# Zio_Qwiic_LoRa_Dev_Board.net
KiCad netlist of a schematic drawn in EAGLE
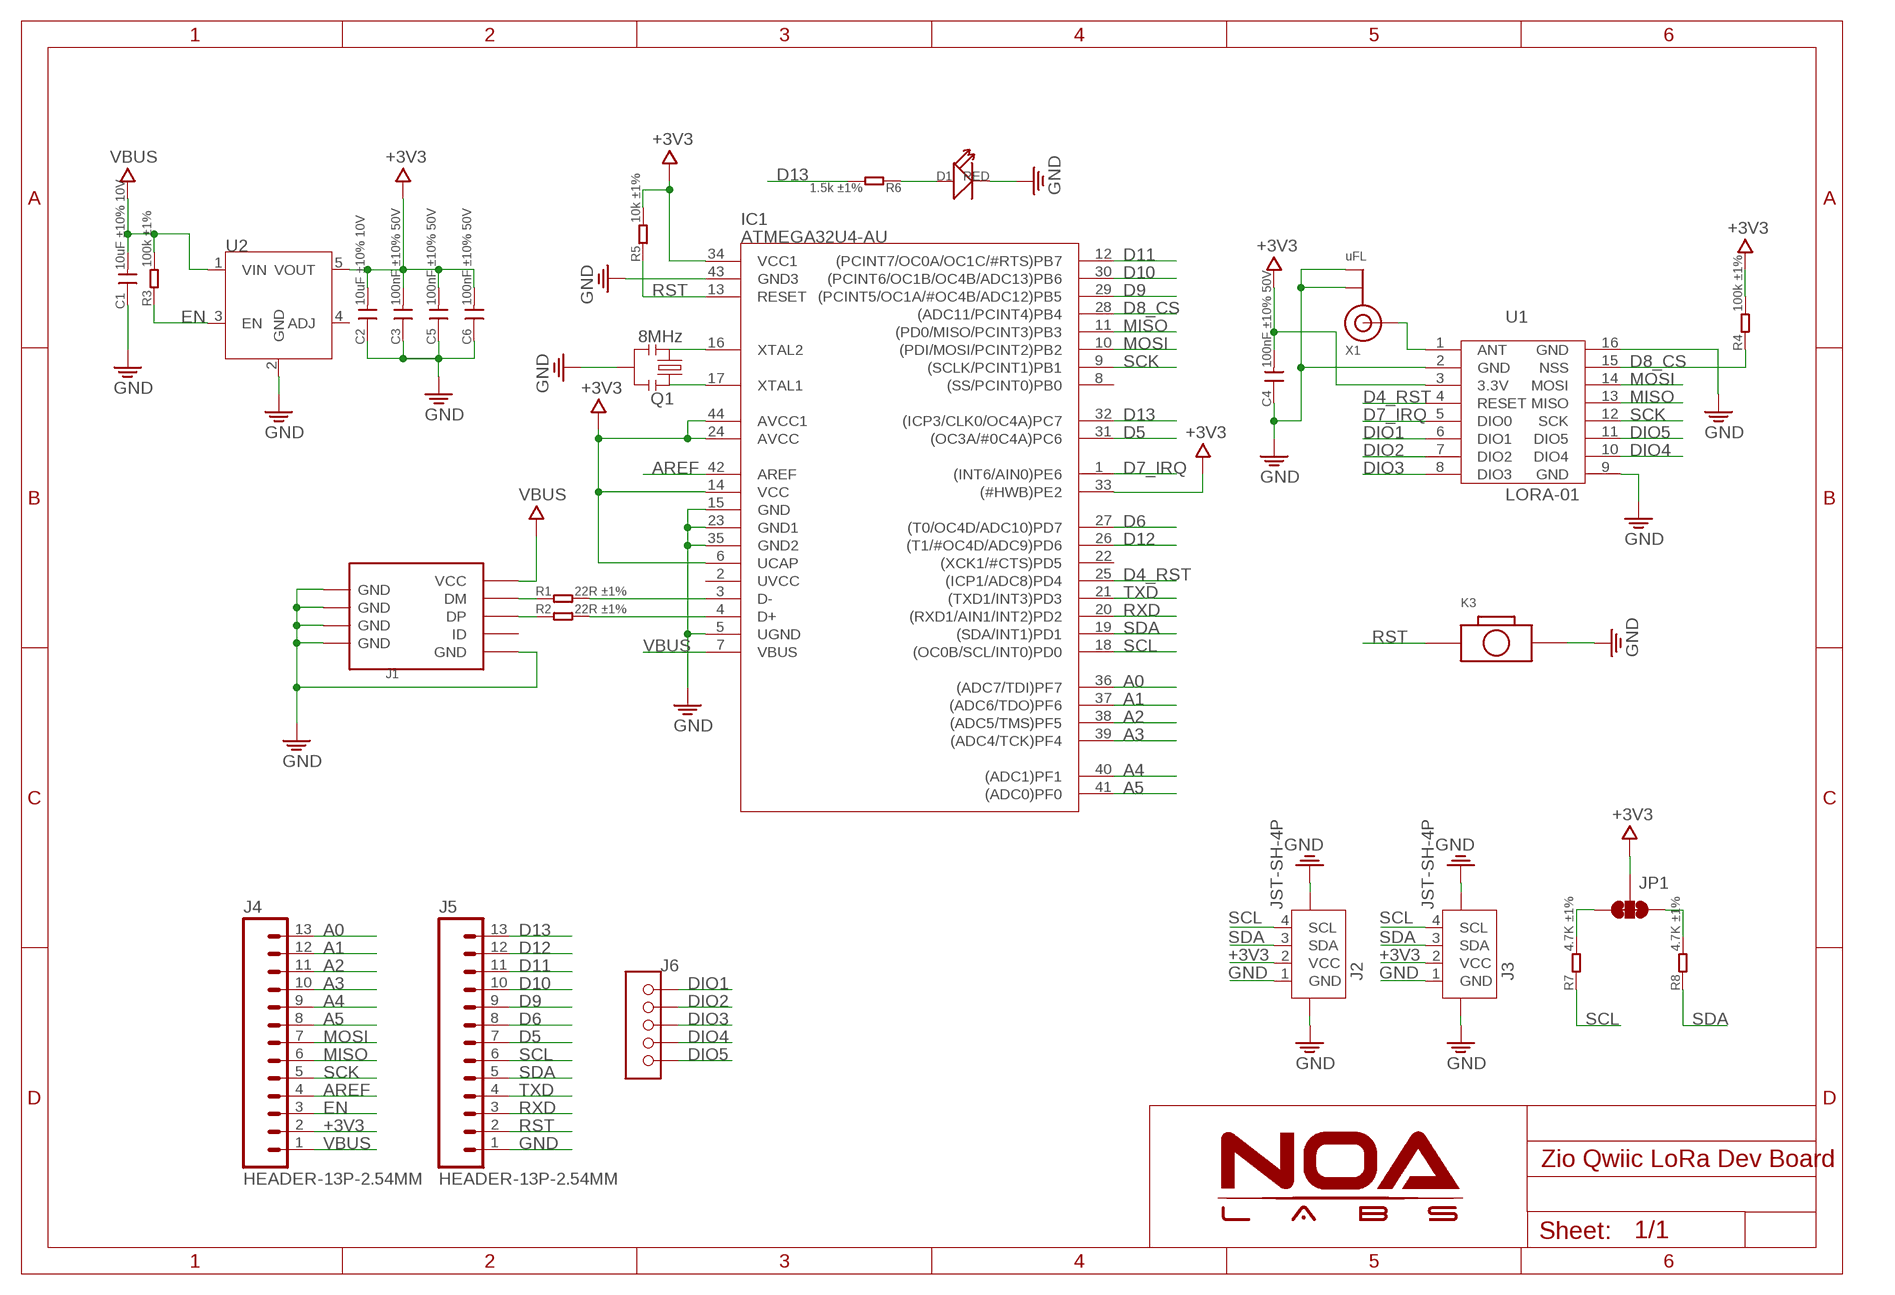
[diagram p0: schematic, sheet 1]

(export (version "E")
  (design (tool "Eeschema 10.0.6"))
  (components
    (comp (ref "C1")
      (value "10uF ±10% 10V")
      (footprint "eagle-import:C0603")
      (libsource (lib "eagle-import") (part "C-0603"))
    )
    (comp (ref "C2")
      (value "10uF ±10% 10V")
      (footprint "eagle-import:C0603")
      (libsource (lib "eagle-import") (part "C-0603"))
    )
    (comp (ref "C3")
      (value "100nF ±10% 50V")
      (footprint "eagle-import:C0603")
      (libsource (lib "eagle-import") (part "C-0603"))
    )
    (comp (ref "C4")
      (value "100nF ±10% 50V")
      (footprint "eagle-import:C0603")
      (libsource (lib "eagle-import") (part "C-0603"))
    )
    (comp (ref "C5")
      (value "100nF ±10% 50V")
      (footprint "eagle-import:C0603")
      (libsource (lib "eagle-import") (part "C-0603"))
    )
    (comp (ref "C6")
      (value "100nF ±10% 50V")
      (footprint "eagle-import:C0603")
      (libsource (lib "eagle-import") (part "C-0603"))
    )
    (comp (ref "D1")
      (value "RED")
      (footprint "eagle-import:LED-0603")
      (libsource (lib "eagle-import") (part "LED'0603'"))
    )
    (comp (ref "IC1")
      (value "ATMEGA32U4-AU")
      (footprint "eagle-import:TQFP44")
      (libsource (lib "eagle-import") (part "ATMEGA32U4"))
    )
    (comp (ref "J1")
      (value "USB-MICROE")
      (footprint "eagle-import:MICRO-SMD")
      (libsource (lib "eagle-import") (part "USB-MICROE"))
    )
    (comp (ref "J2")
      (value "JST-SH-4P")
      (footprint "eagle-import:JST-SH-4P-90")
      (libsource (lib "eagle-import") (part "JST-SH-4P"))
    )
    (comp (ref "J3")
      (value "JST-SH-4P")
      (footprint "eagle-import:JST-SH-4P-90")
      (libsource (lib "eagle-import") (part "JST-SH-4P"))
    )
    (comp (ref "J4")
      (value "HEADER-13P-2.54MM")
      (footprint "eagle-import:13P-SCREW-2.54")
      (libsource (lib "eagle-import") (part "HEADER-13P-2.54MM"))
    )
    (comp (ref "J5")
      (value "HEADER-13P-2.54MM")
      (footprint "eagle-import:13P-SCREW-2.54")
      (libsource (lib "eagle-import") (part "HEADER-13P-2.54MM"))
    )
    (comp (ref "J6")
      (value "HEADER-5P-2.54")
      (footprint "eagle-import:5P-2.54")
      (libsource (lib "eagle-import") (part "HEADER-5P-2.54"))
    )
    (comp (ref "JP1")
      (value "SMT-JUMPER_3_2-NC_TRACE")
      (footprint "eagle-import:SMT-JUMPER_3_2-NC_TRACE")
      (libsource (lib "eagle-import") (part "SMT-JUMPER_3_2-NC_TRACE"))
    )
    (comp (ref "K3")
      (value "BOTTON-2PSKRKAEE020")
      (footprint "eagle-import:SKRKAEE020")
      (libsource (lib "eagle-import") (part "BOTTON-2PSKRKAEE020"))
    )
    (comp (ref "Q1")
      (value "8MHz")
      (footprint "eagle-import:RESONATOR-SMD")
      (libsource (lib "eagle-import") (part "RESONATORSMD"))
    )
    (comp (ref "R1")
      (value "22R ±1%")
      (footprint "eagle-import:R0603")
      (libsource (lib "eagle-import") (part "R-0603"))
    )
    (comp (ref "R2")
      (value "22R ±1%")
      (footprint "eagle-import:R0603")
      (libsource (lib "eagle-import") (part "R-0603"))
    )
    (comp (ref "R3")
      (value "100k ±1%")
      (footprint "eagle-import:R0603")
      (libsource (lib "eagle-import") (part "R-0603"))
    )
    (comp (ref "R4")
      (value "100k ±1%")
      (footprint "eagle-import:R0603")
      (libsource (lib "eagle-import") (part "R-0603"))
    )
    (comp (ref "R5")
      (value "10k ±1%")
      (footprint "eagle-import:R0603")
      (libsource (lib "eagle-import") (part "R-0603"))
    )
    (comp (ref "R6")
      (value "1.5k ±1%")
      (footprint "eagle-import:R0603")
      (libsource (lib "eagle-import") (part "R-0603"))
    )
    (comp (ref "R7")
      (value "4.7K ±1%")
      (footprint "eagle-import:R0603")
      (libsource (lib "eagle-import") (part "R-0603"))
    )
    (comp (ref "R8")
      (value "4.7K ±1%")
      (footprint "eagle-import:R0603")
      (libsource (lib "eagle-import") (part "R-0603"))
    )
    (comp (ref "U1")
      (value "LORA-01")
      (footprint "eagle-import:LORA-01")
      (libsource (lib "eagle-import") (part "LORA-01"))
    )
    (comp (ref "U2")
      (value "AP2112")
      (footprint "eagle-import:SOT23-5")
      (libsource (lib "eagle-import") (part "AP2112"))
    )
    (comp (ref "X1")
      (value "uFL")
      (footprint "eagle-import:U.FL")
      (libsource (lib "eagle-import") (part "ANTENNA_U.FL"))
    )
  )
  (nets
    (net (code "1") (name "+3V3") (class "Default")
      (node (ref "C2") (pin "2") (pinfunction "2_2") (pintype "passive"))
      (node (ref "C3") (pin "2") (pinfunction "2_2") (pintype "passive"))
      (node (ref "C4") (pin "2") (pinfunction "2_2") (pintype "passive"))
      (node (ref "C5") (pin "2") (pinfunction "2_2") (pintype "passive"))
      (node (ref "C6") (pin "2") (pinfunction "2_2") (pintype "passive"))
      (node (ref "IC1") (pin "14") (pinfunction "VCC_14") (pintype "bidirectional"))
      (node (ref "IC1") (pin "24") (pinfunction "AVCC_24") (pintype "bidirectional"))
      (node (ref "IC1") (pin "33") (pinfunction "(#HWB)PE2_33") (pintype "bidirectional"))
      (node (ref "IC1") (pin "34") (pinfunction "VCC1_34") (pintype "bidirectional"))
      (node (ref "IC1") (pin "44") (pinfunction "AVCC1_44") (pintype "bidirectional"))
      (node (ref "IC1") (pin "6") (pinfunction "UCAP_6") (pintype "bidirectional"))
      (node (ref "J2") (pin "2") (pinfunction "VCC_2") (pintype "bidirectional"))
      (node (ref "J3") (pin "2") (pinfunction "VCC_2") (pintype "bidirectional"))
      (node (ref "J4") (pin "2") (pinfunction "2_2") (pintype "passive"))
      (node (ref "JP1") (pin "2") (pinfunction "2_2") (pintype "passive"))
      (node (ref "R4") (pin "2") (pinfunction "2_2") (pintype "passive"))
      (node (ref "R5") (pin "2") (pinfunction "2_2") (pintype "passive"))
      (node (ref "U1") (pin "3") (pinfunction "3.3V_3") (pintype "bidirectional"))
      (node (ref "U2") (pin "5") (pinfunction "VOUT_5") (pintype "bidirectional"))
    )
    (net (code "2") (name "/A0") (class "Default")
      (node (ref "IC1") (pin "36") (pinfunction "(ADC7/TDI)PF7_36") (pintype "bidirectional"))
      (node (ref "J4") (pin "13") (pinfunction "13_13") (pintype "passive"))
    )
    (net (code "3") (name "/A1") (class "Default")
      (node (ref "IC1") (pin "37") (pinfunction "(ADC6/TDO)PF6_37") (pintype "bidirectional"))
      (node (ref "J4") (pin "12") (pinfunction "12_12") (pintype "passive"))
    )
    (net (code "4") (name "/A2") (class "Default")
      (node (ref "IC1") (pin "38") (pinfunction "(ADC5/TMS)PF5_38") (pintype "bidirectional"))
      (node (ref "J4") (pin "11") (pinfunction "11_11") (pintype "passive"))
    )
    (net (code "5") (name "/A3") (class "Default")
      (node (ref "IC1") (pin "39") (pinfunction "(ADC4/TCK)PF4_39") (pintype "bidirectional"))
      (node (ref "J4") (pin "10") (pinfunction "10_10") (pintype "passive"))
    )
    (net (code "6") (name "/A4") (class "Default")
      (node (ref "IC1") (pin "40") (pinfunction "(ADC1)PF1_40") (pintype "bidirectional"))
      (node (ref "J4") (pin "9") (pinfunction "9_9") (pintype "passive"))
    )
    (net (code "7") (name "/A5") (class "Default")
      (node (ref "IC1") (pin "41") (pinfunction "(ADC0)PF0_41") (pintype "bidirectional"))
      (node (ref "J4") (pin "8") (pinfunction "8_8") (pintype "passive"))
    )
    (net (code "8") (name "/AREF") (class "Default")
      (node (ref "IC1") (pin "42") (pinfunction "AREF_42") (pintype "bidirectional"))
      (node (ref "J4") (pin "4") (pinfunction "4_4") (pintype "passive"))
    )
    (net (code "9") (name "/D4_RST") (class "Default")
      (node (ref "IC1") (pin "25") (pinfunction "(ICP1/ADC8)PD4_25") (pintype "bidirectional"))
      (node (ref "U1") (pin "4") (pinfunction "RESET_4") (pintype "bidirectional"))
    )
    (net (code "10") (name "/D5") (class "Default")
      (node (ref "IC1") (pin "31") (pinfunction "(OC3A/#0C4A)PC6_31") (pintype "bidirectional"))
      (node (ref "J5") (pin "7") (pinfunction "7_7") (pintype "passive"))
    )
    (net (code "11") (name "/D6") (class "Default")
      (node (ref "IC1") (pin "27") (pinfunction "(T0/OC4D/ADC10)PD7_27") (pintype "bidirectional"))
      (node (ref "J5") (pin "8") (pinfunction "8_8") (pintype "passive"))
    )
    (net (code "12") (name "/D7_IRQ") (class "Default")
      (node (ref "IC1") (pin "1") (pinfunction "(INT6/AIN0)PE6_1") (pintype "bidirectional"))
      (node (ref "U1") (pin "5") (pinfunction "DIO0_5") (pintype "bidirectional"))
    )
    (net (code "13") (name "/D8_CS") (class "Default")
      (node (ref "IC1") (pin "28") (pinfunction "(ADC11/PCINT4)PB4_28") (pintype "bidirectional"))
      (node (ref "R4") (pin "1") (pinfunction "1_1") (pintype "passive"))
      (node (ref "U1") (pin "15") (pinfunction "NSS_15") (pintype "bidirectional"))
    )
    (net (code "14") (name "/D9") (class "Default")
      (node (ref "IC1") (pin "29") (pinfunction "(PCINT5/OC1A/#OC4B/ADC12)PB5_29") (pintype "bidirectional"))
      (node (ref "J5") (pin "9") (pinfunction "9_9") (pintype "passive"))
    )
    (net (code "15") (name "/D10") (class "Default")
      (node (ref "IC1") (pin "30") (pinfunction "(PCINT6/OC1B/OC4B/ADC13)PB6_30") (pintype "bidirectional"))
      (node (ref "J5") (pin "10") (pinfunction "10_10") (pintype "passive"))
    )
    (net (code "16") (name "/D11") (class "Default")
      (node (ref "IC1") (pin "12") (pinfunction "(PCINT7/OC0A/OC1C/#RTS)PB7_12") (pintype "bidirectional"))
      (node (ref "J5") (pin "11") (pinfunction "11_11") (pintype "passive"))
    )
    (net (code "17") (name "/D12") (class "Default")
      (node (ref "IC1") (pin "26") (pinfunction "(T1/#OC4D/ADC9)PD6_26") (pintype "bidirectional"))
      (node (ref "J5") (pin "12") (pinfunction "12_12") (pintype "passive"))
    )
    (net (code "18") (name "/D13") (class "Default")
      (node (ref "IC1") (pin "32") (pinfunction "(ICP3/CLK0/OC4A)PC7_32") (pintype "bidirectional"))
      (node (ref "J5") (pin "13") (pinfunction "13_13") (pintype "passive"))
      (node (ref "R6") (pin "2") (pinfunction "2_2") (pintype "passive"))
    )
    (net (code "19") (name "/DIO1") (class "Default")
      (node (ref "J6") (pin "1") (pinfunction "1_1") (pintype "bidirectional"))
      (node (ref "U1") (pin "6") (pinfunction "DIO1_6") (pintype "bidirectional"))
    )
    (net (code "20") (name "/DIO2") (class "Default")
      (node (ref "J6") (pin "2") (pinfunction "2_2") (pintype "bidirectional"))
      (node (ref "U1") (pin "7") (pinfunction "DIO2_7") (pintype "bidirectional"))
    )
    (net (code "21") (name "/DIO3") (class "Default")
      (node (ref "J6") (pin "3") (pinfunction "3_3") (pintype "bidirectional"))
      (node (ref "U1") (pin "8") (pinfunction "DIO3_8") (pintype "bidirectional"))
    )
    (net (code "22") (name "/DIO4") (class "Default")
      (node (ref "J6") (pin "4") (pinfunction "4_4") (pintype "bidirectional"))
      (node (ref "U1") (pin "10") (pinfunction "DIO4_10") (pintype "bidirectional"))
    )
    (net (code "23") (name "/DIO5") (class "Default")
      (node (ref "J6") (pin "5") (pinfunction "5_5") (pintype "bidirectional"))
      (node (ref "U1") (pin "11") (pinfunction "DIO5_11") (pintype "bidirectional"))
    )
    (net (code "24") (name "/EN") (class "Default")
      (node (ref "J4") (pin "3") (pinfunction "3_3") (pintype "passive"))
      (node (ref "R3") (pin "1") (pinfunction "1_1") (pintype "passive"))
      (node (ref "U2") (pin "3") (pinfunction "EN_3") (pintype "bidirectional"))
    )
    (net (code "25") (name "/MISO") (class "Default")
      (node (ref "IC1") (pin "11") (pinfunction "(PD0/MISO/PCINT3)PB3_11") (pintype "bidirectional"))
      (node (ref "J4") (pin "6") (pinfunction "6_6") (pintype "passive"))
      (node (ref "U1") (pin "13") (pinfunction "MISO_13") (pintype "bidirectional"))
    )
    (net (code "26") (name "/MOSI") (class "Default")
      (node (ref "IC1") (pin "10") (pinfunction "(PDI/MOSI/PCINT2)PB2_10") (pintype "bidirectional"))
      (node (ref "J4") (pin "7") (pinfunction "7_7") (pintype "passive"))
      (node (ref "U1") (pin "14") (pinfunction "MOSI_14") (pintype "bidirectional"))
    )
    (net (code "27") (name "/RST") (class "Default")
      (node (ref "IC1") (pin "13") (pinfunction "RESET_13") (pintype "bidirectional"))
      (node (ref "J5") (pin "2") (pinfunction "2_2") (pintype "passive"))
      (node (ref "K3") (pin "1") (pinfunction "1_1") (pintype "bidirectional"))
      (node (ref "R5") (pin "1") (pinfunction "1_1") (pintype "passive"))
    )
    (net (code "28") (name "/RXD") (class "Default")
      (node (ref "IC1") (pin "20") (pinfunction "(RXD1/AIN1/INT2)PD2_20") (pintype "bidirectional"))
      (node (ref "J5") (pin "3") (pinfunction "3_3") (pintype "passive"))
    )
    (net (code "29") (name "/SCK") (class "Default")
      (node (ref "IC1") (pin "9") (pinfunction "(SCLK/PCINT1)PB1_9") (pintype "bidirectional"))
      (node (ref "J4") (pin "5") (pinfunction "5_5") (pintype "passive"))
      (node (ref "U1") (pin "12") (pinfunction "SCK_12") (pintype "bidirectional"))
    )
    (net (code "30") (name "/SCL") (class "Default")
      (node (ref "IC1") (pin "18") (pinfunction "(OC0B/SCL/INT0)PD0_18") (pintype "bidirectional"))
      (node (ref "J2") (pin "4") (pinfunction "SCL_4") (pintype "bidirectional"))
      (node (ref "J3") (pin "4") (pinfunction "SCL_4") (pintype "bidirectional"))
      (node (ref "J5") (pin "6") (pinfunction "6_6") (pintype "passive"))
      (node (ref "R7") (pin "1") (pinfunction "1_1") (pintype "passive"))
    )
    (net (code "31") (name "/SDA") (class "Default")
      (node (ref "IC1") (pin "19") (pinfunction "(SDA/INT1)PD1_19") (pintype "bidirectional"))
      (node (ref "J2") (pin "3") (pinfunction "SDA_3") (pintype "bidirectional"))
      (node (ref "J3") (pin "3") (pinfunction "SDA_3") (pintype "bidirectional"))
      (node (ref "J5") (pin "5") (pinfunction "5_5") (pintype "passive"))
      (node (ref "R8") (pin "1") (pinfunction "1_1") (pintype "passive"))
    )
    (net (code "32") (name "/TXD") (class "Default")
      (node (ref "IC1") (pin "21") (pinfunction "(TXD1/INT3)PD3_21") (pintype "bidirectional"))
      (node (ref "J5") (pin "4") (pinfunction "4_4") (pintype "passive"))
    )
    (net (code "33") (name "GND") (class "Default")
      (node (ref "C1") (pin "1") (pinfunction "1_1") (pintype "passive"))
      (node (ref "C2") (pin "1") (pinfunction "1_1") (pintype "passive"))
      (node (ref "C3") (pin "1") (pinfunction "1_1") (pintype "passive"))
      (node (ref "C4") (pin "1") (pinfunction "1_1") (pintype "passive"))
      (node (ref "C5") (pin "1") (pinfunction "1_1") (pintype "passive"))
      (node (ref "C6") (pin "1") (pinfunction "1_1") (pintype "passive"))
      (node (ref "D1") (pin "-") (pinfunction "-_-") (pintype "passive"))
      (node (ref "IC1") (pin "15") (pinfunction "GND_15") (pintype "bidirectional"))
      (node (ref "IC1") (pin "23") (pinfunction "GND1_23") (pintype "bidirectional"))
      (node (ref "IC1") (pin "35") (pinfunction "GND2_35") (pintype "bidirectional"))
      (node (ref "IC1") (pin "43") (pinfunction "GND3_43") (pintype "bidirectional"))
      (node (ref "IC1") (pin "5") (pinfunction "UGND_5") (pintype "bidirectional"))
      (node (ref "J1") (pin "GND") (pinfunction "GND_GND") (pintype "bidirectional"))
      (node (ref "J1") (pin "S1") (pinfunction "GND_S1") (pintype "bidirectional"))
      (node (ref "J1") (pin "S1@1") (pinfunction "GND_S1@1") (pintype "bidirectional"))
      (node (ref "J1") (pin "S1@2") (pinfunction "GND_S1@2") (pintype "bidirectional"))
      (node (ref "J1") (pin "S2") (pinfunction "GND_S2") (pintype "bidirectional"))
      (node (ref "J1") (pin "S2@1") (pinfunction "GND_S2@1") (pintype "bidirectional"))
      (node (ref "J1") (pin "S2@2") (pinfunction "GND_S2@2") (pintype "bidirectional"))
      (node (ref "J1") (pin "S3") (pinfunction "GND_S3") (pintype "bidirectional"))
      (node (ref "J1") (pin "S3@1") (pinfunction "GND_S3@1") (pintype "bidirectional"))
      (node (ref "J1") (pin "S3@2") (pinfunction "GND_S3@2") (pintype "bidirectional"))
      (node (ref "J1") (pin "S4") (pinfunction "GND_S4") (pintype "bidirectional"))
      (node (ref "J1") (pin "S4@1") (pinfunction "GND_S4@1") (pintype "bidirectional"))
      (node (ref "J1") (pin "S4@2") (pinfunction "GND_S4@2") (pintype "bidirectional"))
      (node (ref "J1") (pin "S5") (pinfunction "GND_S5") (pintype "bidirectional"))
      (node (ref "J1") (pin "S6") (pinfunction "GND_S6") (pintype "bidirectional"))
      (node (ref "J2") (pin "1") (pinfunction "GND_1") (pintype "bidirectional"))
      (node (ref "J2") (pin "5") (pinfunction "5_5") (pintype "bidirectional"))
      (node (ref "J2") (pin "6") (pinfunction "6_6") (pintype "bidirectional"))
      (node (ref "J3") (pin "1") (pinfunction "GND_1") (pintype "bidirectional"))
      (node (ref "J3") (pin "5") (pinfunction "5_5") (pintype "bidirectional"))
      (node (ref "J3") (pin "6") (pinfunction "6_6") (pintype "bidirectional"))
      (node (ref "J5") (pin "1") (pinfunction "1_1") (pintype "passive"))
      (node (ref "K3") (pin "2") (pinfunction "2_2") (pintype "bidirectional"))
      (node (ref "Q1") (pin "2") (pinfunction "2_2") (pintype "passive"))
      (node (ref "U1") (pin "16") (pinfunction "GND_16") (pintype "bidirectional"))
      (node (ref "U1") (pin "2") (pinfunction "GND_2") (pintype "bidirectional"))
      (node (ref "U1") (pin "9") (pinfunction "GND_9") (pintype "bidirectional"))
      (node (ref "U2") (pin "2") (pinfunction "GND_2") (pintype "bidirectional"))
      (node (ref "X1") (pin "1") (pinfunction "GND_1") (pintype "passive"))
      (node (ref "X1") (pin "2") (pinfunction "GND_2") (pintype "passive"))
    )
    (net (code "34") (name "Net-(D1-Pad+)") (class "Default")
      (node (ref "D1") (pin "+") (pinfunction "+_+") (pintype "passive"))
      (node (ref "R6") (pin "1") (pinfunction "1_1") (pintype "passive"))
    )
    (net (code "35") (name "Net-(IC1-D+)") (class "Default")
      (node (ref "IC1") (pin "4") (pinfunction "D+_4") (pintype "bidirectional"))
      (node (ref "R2") (pin "2") (pinfunction "2_2") (pintype "passive"))
    )
    (net (code "36") (name "Net-(IC1-D-)") (class "Default")
      (node (ref "IC1") (pin "3") (pinfunction "D-_3") (pintype "bidirectional"))
      (node (ref "R1") (pin "2") (pinfunction "2_2") (pintype "passive"))
    )
    (net (code "37") (name "Net-(IC1-XTAL1)") (class "Default")
      (node (ref "IC1") (pin "17") (pinfunction "XTAL1_17") (pintype "bidirectional"))
      (node (ref "Q1") (pin "1") (pinfunction "1_1") (pintype "passive"))
    )
    (net (code "38") (name "Net-(IC1-XTAL2)") (class "Default")
      (node (ref "IC1") (pin "16") (pinfunction "XTAL2_16") (pintype "bidirectional"))
      (node (ref "Q1") (pin "3") (pinfunction "3_3") (pintype "passive"))
    )
    (net (code "39") (name "Net-(J1-DM)") (class "Default")
      (node (ref "J1") (pin "D-") (pinfunction "DM_D-") (pintype "bidirectional"))
      (node (ref "R1") (pin "1") (pinfunction "1_1") (pintype "passive"))
    )
    (net (code "40") (name "Net-(J1-DP)") (class "Default")
      (node (ref "J1") (pin "D+") (pinfunction "DP_D+") (pintype "bidirectional"))
      (node (ref "R2") (pin "1") (pinfunction "1_1") (pintype "passive"))
    )
    (net (code "41") (name "Net-(JP1-Pad1)") (class "Default")
      (node (ref "JP1") (pin "1") (pinfunction "1_1") (pintype "passive"))
      (node (ref "R8") (pin "2") (pinfunction "2_2") (pintype "passive"))
    )
    (net (code "42") (name "Net-(JP1-Pad3)") (class "Default")
      (node (ref "JP1") (pin "3") (pinfunction "3_3") (pintype "passive"))
      (node (ref "R7") (pin "2") (pinfunction "2_2") (pintype "passive"))
    )
    (net (code "43") (name "Net-(U1-ANT)") (class "Default")
      (node (ref "U1") (pin "1") (pinfunction "ANT_1") (pintype "bidirectional"))
      (node (ref "X1") (pin "3") (pinfunction "SIGNAL_3") (pintype "passive"))
    )
    (net (code "44") (name "VBUS") (class "Default")
      (node (ref "C1") (pin "2") (pinfunction "2_2") (pintype "passive"))
      (node (ref "IC1") (pin "7") (pinfunction "VBUS_7") (pintype "bidirectional"))
      (node (ref "J1") (pin "VBUS") (pinfunction "VCC_VBUS") (pintype "bidirectional"))
      (node (ref "J4") (pin "1") (pinfunction "1_1") (pintype "passive"))
      (node (ref "R3") (pin "2") (pinfunction "2_2") (pintype "passive"))
      (node (ref "U2") (pin "1") (pinfunction "VIN_1") (pintype "bidirectional"))
    )
    (net (code "45") (name "unconnected-(IC1-(SS{slash}PCINT0)PB0-Pad8)") (class "Default")
      (node (ref "IC1") (pin "8") (pinfunction "(SS/PCINT0)PB0_8") (pintype "bidirectional"))
    )
    (net (code "46") (name "unconnected-(IC1-(XCK1{slash}#CTS)PD5-Pad22)") (class "Default")
      (node (ref "IC1") (pin "22") (pinfunction "(XCK1/#CTS)PD5_22") (pintype "bidirectional"))
    )
    (net (code "47") (name "unconnected-(IC1-UVCC-Pad2)") (class "Default")
      (node (ref "IC1") (pin "2") (pinfunction "UVCC_2") (pintype "bidirectional"))
    )
    (net (code "48") (name "unconnected-(J1-PadID)") (class "Default")
      (node (ref "J1") (pin "ID") (pinfunction "ID_ID") (pintype "bidirectional"))
    )
    (net (code "49") (name "unconnected-(U2-ADJ-Pad4)") (class "Default")
      (node (ref "U2") (pin "4") (pinfunction "ADJ_4") (pintype "bidirectional"))
    )
  )
)
